# DESIGN7MP_Schematic.net
KiCad netlist of a schematic drawn in EAGLE
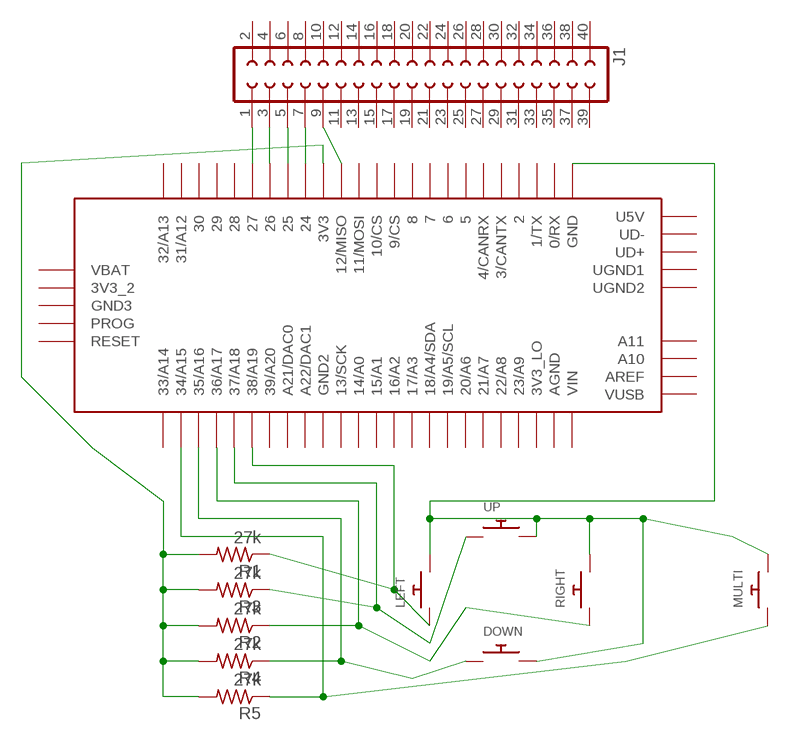
[diagram p0: schematic, sheet 1]

(export (version "E")
  (design (tool "Eeschema 10.0.6"))
  (components
    (comp (ref "DOWN")
      (value "SWITCH_PUSHBUTTONEVQ-PE")
      (footprint "eagle-import:TACT_PANA-EVQ")
      (libsource (lib "eagle-import") (part "SWITCH_PUSHBUTTONEVQ-PE"))
    )
    (comp (ref "J1")
      (value "SOCKET-40V")
      (footprint "eagle-import:S40V")
      (libsource (lib "eagle-import") (part "SOCKET-40V"))
    )
    (comp (ref "LEFT")
      (value "SWITCH_PUSHBUTTONEVQ-PE")
      (footprint "eagle-import:TACT_PANA-EVQ")
      (libsource (lib "eagle-import") (part "SWITCH_PUSHBUTTONEVQ-PE"))
    )
    (comp (ref "MULTI")
      (value "SWITCH_PUSHBUTTONEVQ-PE")
      (footprint "eagle-import:TACT_PANA-EVQ")
      (libsource (lib "eagle-import") (part "SWITCH_PUSHBUTTONEVQ-PE"))
    )
    (comp (ref "R1")
      (value "27k")
      (footprint "eagle-import:0204_5")
      (libsource (lib "eagle-import") (part "R-US_0204/5"))
    )
    (comp (ref "R2")
      (value "27k")
      (footprint "eagle-import:0204_5")
      (libsource (lib "eagle-import") (part "R-US_0204/5"))
    )
    (comp (ref "R3")
      (value "27k")
      (footprint "eagle-import:0204_5")
      (libsource (lib "eagle-import") (part "R-US_0204/5"))
    )
    (comp (ref "R4")
      (value "27k")
      (footprint "eagle-import:0204_5")
      (libsource (lib "eagle-import") (part "R-US_0204/5"))
    )
    (comp (ref "R5")
      (value "27k")
      (footprint "eagle-import:0204_5")
      (libsource (lib "eagle-import") (part "R-US_0204/5"))
    )
    (comp (ref "RIGHT")
      (value "SWITCH_PUSHBUTTONEVQ-PE")
      (footprint "eagle-import:TACT_PANA-EVQ")
      (libsource (lib "eagle-import") (part "SWITCH_PUSHBUTTONEVQ-PE"))
    )
    (comp (ref "U$1")
      (value "TEENSY_3.5/3.6")
      (footprint "eagle-import:TEENSY_3.5_3.6")
      (libsource (lib "eagle-import") (part "TEENSY_3.5/3.6"))
    )
    (comp (ref "UP")
      (value "SWITCH_PUSHBUTTONEVQ-PE")
      (footprint "eagle-import:TACT_PANA-EVQ")
      (libsource (lib "eagle-import") (part "SWITCH_PUSHBUTTONEVQ-PE"))
    )
  )
  (nets
    (net (code "1") (name "Net-(DOWN-PadP$1)") (class "Default")
      (node (ref "DOWN") (pin "P$1") (pinfunction "P$1_P$1") (pintype "passive"))
      (node (ref "R4") (pin "1") (pinfunction "1_1") (pintype "passive"))
      (node (ref "U$1") (pin "35/A16") (pinfunction "35/A16_35/A16") (pintype "bidirectional"))
    )
    (net (code "2") (name "Net-(DOWN-PadP$2)") (class "Default")
      (node (ref "DOWN") (pin "P$2") (pinfunction "P$2_P$2") (pintype "passive"))
      (node (ref "LEFT") (pin "P$2") (pinfunction "P$2_P$2") (pintype "passive"))
      (node (ref "MULTI") (pin "P$2") (pinfunction "P$2_P$2") (pintype "passive"))
      (node (ref "RIGHT") (pin "P$2") (pinfunction "P$2_P$2") (pintype "passive"))
      (node (ref "U$1") (pin "GND") (pinfunction "GND_GND") (pintype "bidirectional"))
      (node (ref "UP") (pin "P$2") (pinfunction "P$2_P$2") (pintype "passive"))
    )
    (net (code "3") (name "Net-(J1-Pad1)") (class "Default")
      (node (ref "J1") (pin "1") (pinfunction "1_1") (pintype "passive"))
      (node (ref "U$1") (pin "27") (pinfunction "27_27") (pintype "bidirectional"))
    )
    (net (code "4") (name "Net-(J1-Pad3)") (class "Default")
      (node (ref "J1") (pin "3") (pinfunction "3_3") (pintype "passive"))
      (node (ref "U$1") (pin "26") (pinfunction "26_26") (pintype "bidirectional"))
    )
    (net (code "5") (name "Net-(J1-Pad5)") (class "Default")
      (node (ref "J1") (pin "5") (pinfunction "5_5") (pintype "passive"))
      (node (ref "U$1") (pin "25") (pinfunction "25_25") (pintype "bidirectional"))
    )
    (net (code "6") (name "Net-(J1-Pad7)") (class "Default")
      (node (ref "J1") (pin "7") (pinfunction "7_7") (pintype "passive"))
      (node (ref "U$1") (pin "24") (pinfunction "24_24") (pintype "bidirectional"))
    )
    (net (code "7") (name "Net-(J1-Pad9)") (class "Default")
      (node (ref "J1") (pin "9") (pinfunction "9_9") (pintype "passive"))
      (node (ref "U$1") (pin "12/MISO") (pinfunction "12/MISO_12/MISO") (pintype "bidirectional"))
    )
    (net (code "8") (name "Net-(LEFT-PadP$1)") (class "Default")
      (node (ref "LEFT") (pin "P$1") (pinfunction "P$1_P$1") (pintype "passive"))
      (node (ref "R1") (pin "1") (pinfunction "1_1") (pintype "passive"))
      (node (ref "U$1") (pin "38/A19") (pinfunction "38/A19_38/A19") (pintype "bidirectional"))
    )
    (net (code "9") (name "Net-(MULTI-PadP$1)") (class "Default")
      (node (ref "MULTI") (pin "P$1") (pinfunction "P$1_P$1") (pintype "passive"))
      (node (ref "R5") (pin "1") (pinfunction "1_1") (pintype "passive"))
      (node (ref "U$1") (pin "34/A15") (pinfunction "34/A15_34/A15") (pintype "bidirectional"))
    )
    (net (code "10") (name "Net-(R1-Pad2)") (class "Default")
      (node (ref "R1") (pin "2") (pinfunction "2_2") (pintype "passive"))
      (node (ref "R2") (pin "2") (pinfunction "2_2") (pintype "passive"))
      (node (ref "R3") (pin "2") (pinfunction "2_2") (pintype "passive"))
      (node (ref "R4") (pin "2") (pinfunction "2_2") (pintype "passive"))
      (node (ref "R5") (pin "2") (pinfunction "2_2") (pintype "passive"))
      (node (ref "U$1") (pin "3V3") (pinfunction "3V3_3V3") (pintype "bidirectional"))
    )
    (net (code "11") (name "Net-(R2-Pad1)") (class "Default")
      (node (ref "R2") (pin "1") (pinfunction "1_1") (pintype "passive"))
      (node (ref "RIGHT") (pin "P$1") (pinfunction "P$1_P$1") (pintype "passive"))
      (node (ref "U$1") (pin "36/A17") (pinfunction "36/A17_36/A17") (pintype "bidirectional"))
    )
    (net (code "12") (name "Net-(R3-Pad1)") (class "Default")
      (node (ref "R3") (pin "1") (pinfunction "1_1") (pintype "passive"))
      (node (ref "U$1") (pin "37/A18") (pinfunction "37/A18_37/A18") (pintype "bidirectional"))
      (node (ref "UP") (pin "P$1") (pinfunction "P$1_P$1") (pintype "passive"))
    )
    (net (code "13") (name "unconnected-(J1-Pad2)") (class "Default")
      (node (ref "J1") (pin "2") (pinfunction "2_2") (pintype "passive"))
    )
    (net (code "14") (name "unconnected-(J1-Pad4)") (class "Default")
      (node (ref "J1") (pin "4") (pinfunction "4_4") (pintype "passive"))
    )
    (net (code "15") (name "unconnected-(J1-Pad6)") (class "Default")
      (node (ref "J1") (pin "6") (pinfunction "6_6") (pintype "passive"))
    )
    (net (code "16") (name "unconnected-(J1-Pad8)") (class "Default")
      (node (ref "J1") (pin "8") (pinfunction "8_8") (pintype "passive"))
    )
    (net (code "17") (name "unconnected-(J1-Pad10)") (class "Default")
      (node (ref "J1") (pin "10") (pinfunction "10_10") (pintype "passive"))
    )
    (net (code "18") (name "unconnected-(J1-Pad11)") (class "Default")
      (node (ref "J1") (pin "11") (pinfunction "11_11") (pintype "passive"))
    )
    (net (code "19") (name "unconnected-(J1-Pad12)") (class "Default")
      (node (ref "J1") (pin "12") (pinfunction "12_12") (pintype "passive"))
    )
    (net (code "20") (name "unconnected-(J1-Pad13)") (class "Default")
      (node (ref "J1") (pin "13") (pinfunction "13_13") (pintype "passive"))
    )
    (net (code "21") (name "unconnected-(J1-Pad14)") (class "Default")
      (node (ref "J1") (pin "14") (pinfunction "14_14") (pintype "passive"))
    )
    (net (code "22") (name "unconnected-(J1-Pad15)") (class "Default")
      (node (ref "J1") (pin "15") (pinfunction "15_15") (pintype "passive"))
    )
    (net (code "23") (name "unconnected-(J1-Pad16)") (class "Default")
      (node (ref "J1") (pin "16") (pinfunction "16_16") (pintype "passive"))
    )
    (net (code "24") (name "unconnected-(J1-Pad17)") (class "Default")
      (node (ref "J1") (pin "17") (pinfunction "17_17") (pintype "passive"))
    )
    (net (code "25") (name "unconnected-(J1-Pad18)") (class "Default")
      (node (ref "J1") (pin "18") (pinfunction "18_18") (pintype "passive"))
    )
    (net (code "26") (name "unconnected-(J1-Pad19)") (class "Default")
      (node (ref "J1") (pin "19") (pinfunction "19_19") (pintype "passive"))
    )
    (net (code "27") (name "unconnected-(J1-Pad20)") (class "Default")
      (node (ref "J1") (pin "20") (pinfunction "20_20") (pintype "passive"))
    )
    (net (code "28") (name "unconnected-(J1-Pad21)") (class "Default")
      (node (ref "J1") (pin "21") (pinfunction "21_21") (pintype "passive"))
    )
    (net (code "29") (name "unconnected-(J1-Pad22)") (class "Default")
      (node (ref "J1") (pin "22") (pinfunction "22_22") (pintype "passive"))
    )
    (net (code "30") (name "unconnected-(J1-Pad23)") (class "Default")
      (node (ref "J1") (pin "23") (pinfunction "23_23") (pintype "passive"))
    )
    (net (code "31") (name "unconnected-(J1-Pad24)") (class "Default")
      (node (ref "J1") (pin "24") (pinfunction "24_24") (pintype "passive"))
    )
    (net (code "32") (name "unconnected-(J1-Pad25)") (class "Default")
      (node (ref "J1") (pin "25") (pinfunction "25_25") (pintype "passive"))
    )
    (net (code "33") (name "unconnected-(J1-Pad26)") (class "Default")
      (node (ref "J1") (pin "26") (pinfunction "26_26") (pintype "passive"))
    )
    (net (code "34") (name "unconnected-(J1-Pad27)") (class "Default")
      (node (ref "J1") (pin "27") (pinfunction "27_27") (pintype "passive"))
    )
    (net (code "35") (name "unconnected-(J1-Pad28)") (class "Default")
      (node (ref "J1") (pin "28") (pinfunction "28_28") (pintype "passive"))
    )
    (net (code "36") (name "unconnected-(J1-Pad29)") (class "Default")
      (node (ref "J1") (pin "29") (pinfunction "29_29") (pintype "passive"))
    )
    (net (code "37") (name "unconnected-(J1-Pad30)") (class "Default")
      (node (ref "J1") (pin "30") (pinfunction "30_30") (pintype "passive"))
    )
    (net (code "38") (name "unconnected-(J1-Pad31)") (class "Default")
      (node (ref "J1") (pin "31") (pinfunction "31_31") (pintype "passive"))
    )
    (net (code "39") (name "unconnected-(J1-Pad32)") (class "Default")
      (node (ref "J1") (pin "32") (pinfunction "32_32") (pintype "passive"))
    )
    (net (code "40") (name "unconnected-(J1-Pad33)") (class "Default")
      (node (ref "J1") (pin "33") (pinfunction "33_33") (pintype "passive"))
    )
    (net (code "41") (name "unconnected-(J1-Pad34)") (class "Default")
      (node (ref "J1") (pin "34") (pinfunction "34_34") (pintype "passive"))
    )
    (net (code "42") (name "unconnected-(J1-Pad35)") (class "Default")
      (node (ref "J1") (pin "35") (pinfunction "35_35") (pintype "passive"))
    )
    (net (code "43") (name "unconnected-(J1-Pad36)") (class "Default")
      (node (ref "J1") (pin "36") (pinfunction "36_36") (pintype "passive"))
    )
    (net (code "44") (name "unconnected-(J1-Pad37)") (class "Default")
      (node (ref "J1") (pin "37") (pinfunction "37_37") (pintype "passive"))
    )
    (net (code "45") (name "unconnected-(J1-Pad38)") (class "Default")
      (node (ref "J1") (pin "38") (pinfunction "38_38") (pintype "passive"))
    )
    (net (code "46") (name "unconnected-(J1-Pad39)") (class "Default")
      (node (ref "J1") (pin "39") (pinfunction "39_39") (pintype "passive"))
    )
    (net (code "47") (name "unconnected-(J1-Pad40)") (class "Default")
      (node (ref "J1") (pin "40") (pinfunction "40_40") (pintype "passive"))
    )
    (net (code "48") (name "unconnected-(U$1-A21{slash}DAC0-Pad21{slash}DAC0)") (class "Default")
      (node (ref "U$1") (pin "21/DAC0") (pinfunction "A21/DAC0_21/DAC0") (pintype "bidirectional"))
    )
    (net (code "49") (name "unconnected-(U$1-Pad0{slash}RX)") (class "Default")
      (node (ref "U$1") (pin "0/RX") (pinfunction "0/RX_0/RX") (pintype "bidirectional"))
    )
    (net (code "50") (name "unconnected-(U$1-Pad1{slash}TX)") (class "Default")
      (node (ref "U$1") (pin "1/TX") (pinfunction "1/TX_1/TX") (pintype "bidirectional"))
    )
    (net (code "51") (name "unconnected-(U$1-Pad2)") (class "Default")
      (node (ref "U$1") (pin "2") (pinfunction "2_2") (pintype "bidirectional"))
    )
    (net (code "52") (name "unconnected-(U$1-Pad3V3_2)") (class "Default")
      (node (ref "U$1") (pin "3V3_2") (pinfunction "3V3_2_3V3_2") (pintype "bidirectional"))
    )
    (net (code "53") (name "unconnected-(U$1-Pad3V3_LO)") (class "Default")
      (node (ref "U$1") (pin "3V3_LO") (pinfunction "3V3_LO_3V3_LO") (pintype "bidirectional"))
    )
    (net (code "54") (name "unconnected-(U$1-Pad3{slash}CANTX)") (class "Default")
      (node (ref "U$1") (pin "3/CANTX") (pinfunction "3/CANTX_3/CANTX") (pintype "bidirectional"))
    )
    (net (code "55") (name "unconnected-(U$1-Pad4{slash}CANRX)") (class "Default")
      (node (ref "U$1") (pin "4/CANRX") (pinfunction "4/CANRX_4/CANRX") (pintype "bidirectional"))
    )
    (net (code "56") (name "unconnected-(U$1-Pad5)") (class "Default")
      (node (ref "U$1") (pin "5") (pinfunction "5_5") (pintype "bidirectional"))
    )
    (net (code "57") (name "unconnected-(U$1-Pad6)") (class "Default")
      (node (ref "U$1") (pin "6") (pinfunction "6_6") (pintype "bidirectional"))
    )
    (net (code "58") (name "unconnected-(U$1-Pad7)") (class "Default")
      (node (ref "U$1") (pin "7") (pinfunction "7_7") (pintype "bidirectional"))
    )
    (net (code "59") (name "unconnected-(U$1-Pad8)") (class "Default")
      (node (ref "U$1") (pin "8") (pinfunction "8_8") (pintype "bidirectional"))
    )
    (net (code "60") (name "unconnected-(U$1-Pad9{slash}CS)") (class "Default")
      (node (ref "U$1") (pin "9/CS") (pinfunction "9/CS_9/CS") (pintype "bidirectional"))
    )
    (net (code "61") (name "unconnected-(U$1-Pad10{slash}CS)") (class "Default")
      (node (ref "U$1") (pin "10/CS") (pinfunction "10/CS_10/CS") (pintype "bidirectional"))
    )
    (net (code "62") (name "unconnected-(U$1-Pad11{slash}MOSI)") (class "Default")
      (node (ref "U$1") (pin "11/MOSI") (pinfunction "11/MOSI_11/MOSI") (pintype "bidirectional"))
    )
    (net (code "63") (name "unconnected-(U$1-Pad13{slash}SCK)") (class "Default")
      (node (ref "U$1") (pin "13/SCK") (pinfunction "13/SCK_13/SCK") (pintype "bidirectional"))
    )
    (net (code "64") (name "unconnected-(U$1-Pad14{slash}A0)") (class "Default")
      (node (ref "U$1") (pin "14/A0") (pinfunction "14/A0_14/A0") (pintype "bidirectional"))
    )
    (net (code "65") (name "unconnected-(U$1-Pad15{slash}A1)") (class "Default")
      (node (ref "U$1") (pin "15/A1") (pinfunction "15/A1_15/A1") (pintype "bidirectional"))
    )
    (net (code "66") (name "unconnected-(U$1-Pad16{slash}A2)") (class "Default")
      (node (ref "U$1") (pin "16/A2") (pinfunction "16/A2_16/A2") (pintype "bidirectional"))
    )
    (net (code "67") (name "unconnected-(U$1-Pad17{slash}A3)") (class "Default")
      (node (ref "U$1") (pin "17/A3") (pinfunction "17/A3_17/A3") (pintype "bidirectional"))
    )
    (net (code "68") (name "unconnected-(U$1-Pad18{slash}A4{slash}SDA)") (class "Default")
      (node (ref "U$1") (pin "18/A4/SDA") (pinfunction "18/A4/SDA_18/A4/SDA") (pintype "bidirectional"))
    )
    (net (code "69") (name "unconnected-(U$1-Pad19{slash}A5{slash}SCL)") (class "Default")
      (node (ref "U$1") (pin "19/A5/SCL") (pinfunction "19/A5/SCL_19/A5/SCL") (pintype "bidirectional"))
    )
    (net (code "70") (name "unconnected-(U$1-Pad20{slash}A6)") (class "Default")
      (node (ref "U$1") (pin "20/A6") (pinfunction "20/A6_20/A6") (pintype "bidirectional"))
    )
    (net (code "71") (name "unconnected-(U$1-Pad21{slash}A7)") (class "Default")
      (node (ref "U$1") (pin "21/A7") (pinfunction "21/A7_21/A7") (pintype "bidirectional"))
    )
    (net (code "72") (name "unconnected-(U$1-Pad22{slash}A8)") (class "Default")
      (node (ref "U$1") (pin "22/A8") (pinfunction "22/A8_22/A8") (pintype "bidirectional"))
    )
    (net (code "73") (name "unconnected-(U$1-Pad23{slash}A9)") (class "Default")
      (node (ref "U$1") (pin "23/A9") (pinfunction "23/A9_23/A9") (pintype "bidirectional"))
    )
    (net (code "74") (name "unconnected-(U$1-Pad28)") (class "Default")
      (node (ref "U$1") (pin "28") (pinfunction "28_28") (pintype "bidirectional"))
    )
    (net (code "75") (name "unconnected-(U$1-Pad29)") (class "Default")
      (node (ref "U$1") (pin "29") (pinfunction "29_29") (pintype "bidirectional"))
    )
    (net (code "76") (name "unconnected-(U$1-Pad30)") (class "Default")
      (node (ref "U$1") (pin "30") (pinfunction "30_30") (pintype "bidirectional"))
    )
    (net (code "77") (name "unconnected-(U$1-Pad31{slash}A12)") (class "Default")
      (node (ref "U$1") (pin "31/A12") (pinfunction "31/A12_31/A12") (pintype "bidirectional"))
    )
    (net (code "78") (name "unconnected-(U$1-Pad32{slash}A13)") (class "Default")
      (node (ref "U$1") (pin "32/A13") (pinfunction "32/A13_32/A13") (pintype "bidirectional"))
    )
    (net (code "79") (name "unconnected-(U$1-Pad33{slash}A14)") (class "Default")
      (node (ref "U$1") (pin "33/A14") (pinfunction "33/A14_33/A14") (pintype "bidirectional"))
    )
    (net (code "80") (name "unconnected-(U$1-Pad39{slash}A20)") (class "Default")
      (node (ref "U$1") (pin "39/A20") (pinfunction "39/A20_39/A20") (pintype "bidirectional"))
    )
    (net (code "81") (name "unconnected-(U$1-PadA10)") (class "Default")
      (node (ref "U$1") (pin "A10") (pinfunction "A10_A10") (pintype "bidirectional"))
    )
    (net (code "82") (name "unconnected-(U$1-PadA11)") (class "Default")
      (node (ref "U$1") (pin "A11") (pinfunction "A11_A11") (pintype "bidirectional"))
    )
    (net (code "83") (name "unconnected-(U$1-PadA22{slash}DAC1)") (class "Default")
      (node (ref "U$1") (pin "A22/DAC1") (pinfunction "A22/DAC1_A22/DAC1") (pintype "bidirectional"))
    )
    (net (code "84") (name "unconnected-(U$1-PadAGND)") (class "Default")
      (node (ref "U$1") (pin "AGND") (pinfunction "AGND_AGND") (pintype "bidirectional"))
    )
    (net (code "85") (name "unconnected-(U$1-PadAREF)") (class "Default")
      (node (ref "U$1") (pin "AREF") (pinfunction "AREF_AREF") (pintype "bidirectional"))
    )
    (net (code "86") (name "unconnected-(U$1-PadGND2)") (class "Default")
      (node (ref "U$1") (pin "GND2") (pinfunction "GND2_GND2") (pintype "bidirectional"))
    )
    (net (code "87") (name "unconnected-(U$1-PadGND3)") (class "Default")
      (node (ref "U$1") (pin "GND3") (pinfunction "GND3_GND3") (pintype "bidirectional"))
    )
    (net (code "88") (name "unconnected-(U$1-PadPROG)") (class "Default")
      (node (ref "U$1") (pin "PROG") (pinfunction "PROG_PROG") (pintype "bidirectional"))
    )
    (net (code "89") (name "unconnected-(U$1-PadRESET)") (class "Default")
      (node (ref "U$1") (pin "RESET") (pinfunction "RESET_RESET") (pintype "bidirectional"))
    )
    (net (code "90") (name "unconnected-(U$1-PadU5V)") (class "Default")
      (node (ref "U$1") (pin "U5V") (pinfunction "U5V_U5V") (pintype "bidirectional"))
    )
    (net (code "91") (name "unconnected-(U$1-PadUD+)") (class "Default")
      (node (ref "U$1") (pin "UD+") (pinfunction "UD+_UD+") (pintype "bidirectional"))
    )
    (net (code "92") (name "unconnected-(U$1-PadUD-)") (class "Default")
      (node (ref "U$1") (pin "UD-") (pinfunction "UD-_UD-") (pintype "bidirectional"))
    )
    (net (code "93") (name "unconnected-(U$1-PadUGND1)") (class "Default")
      (node (ref "U$1") (pin "UGND1") (pinfunction "UGND1_UGND1") (pintype "bidirectional"))
    )
    (net (code "94") (name "unconnected-(U$1-PadUGND2)") (class "Default")
      (node (ref "U$1") (pin "UGND2") (pinfunction "UGND2_UGND2") (pintype "bidirectional"))
    )
    (net (code "95") (name "unconnected-(U$1-PadVBAT)") (class "Default")
      (node (ref "U$1") (pin "VBAT") (pinfunction "VBAT_VBAT") (pintype "bidirectional"))
    )
    (net (code "96") (name "unconnected-(U$1-PadVIN)") (class "Default")
      (node (ref "U$1") (pin "VIN") (pinfunction "VIN_VIN") (pintype "bidirectional"))
    )
    (net (code "97") (name "unconnected-(U$1-PadVUSB)") (class "Default")
      (node (ref "U$1") (pin "VUSB") (pinfunction "VUSB_VUSB") (pintype "bidirectional"))
    )
  )
)
